# IMX8_PWR.net
KiCad netlist of a schematic drawn in Altium Designer
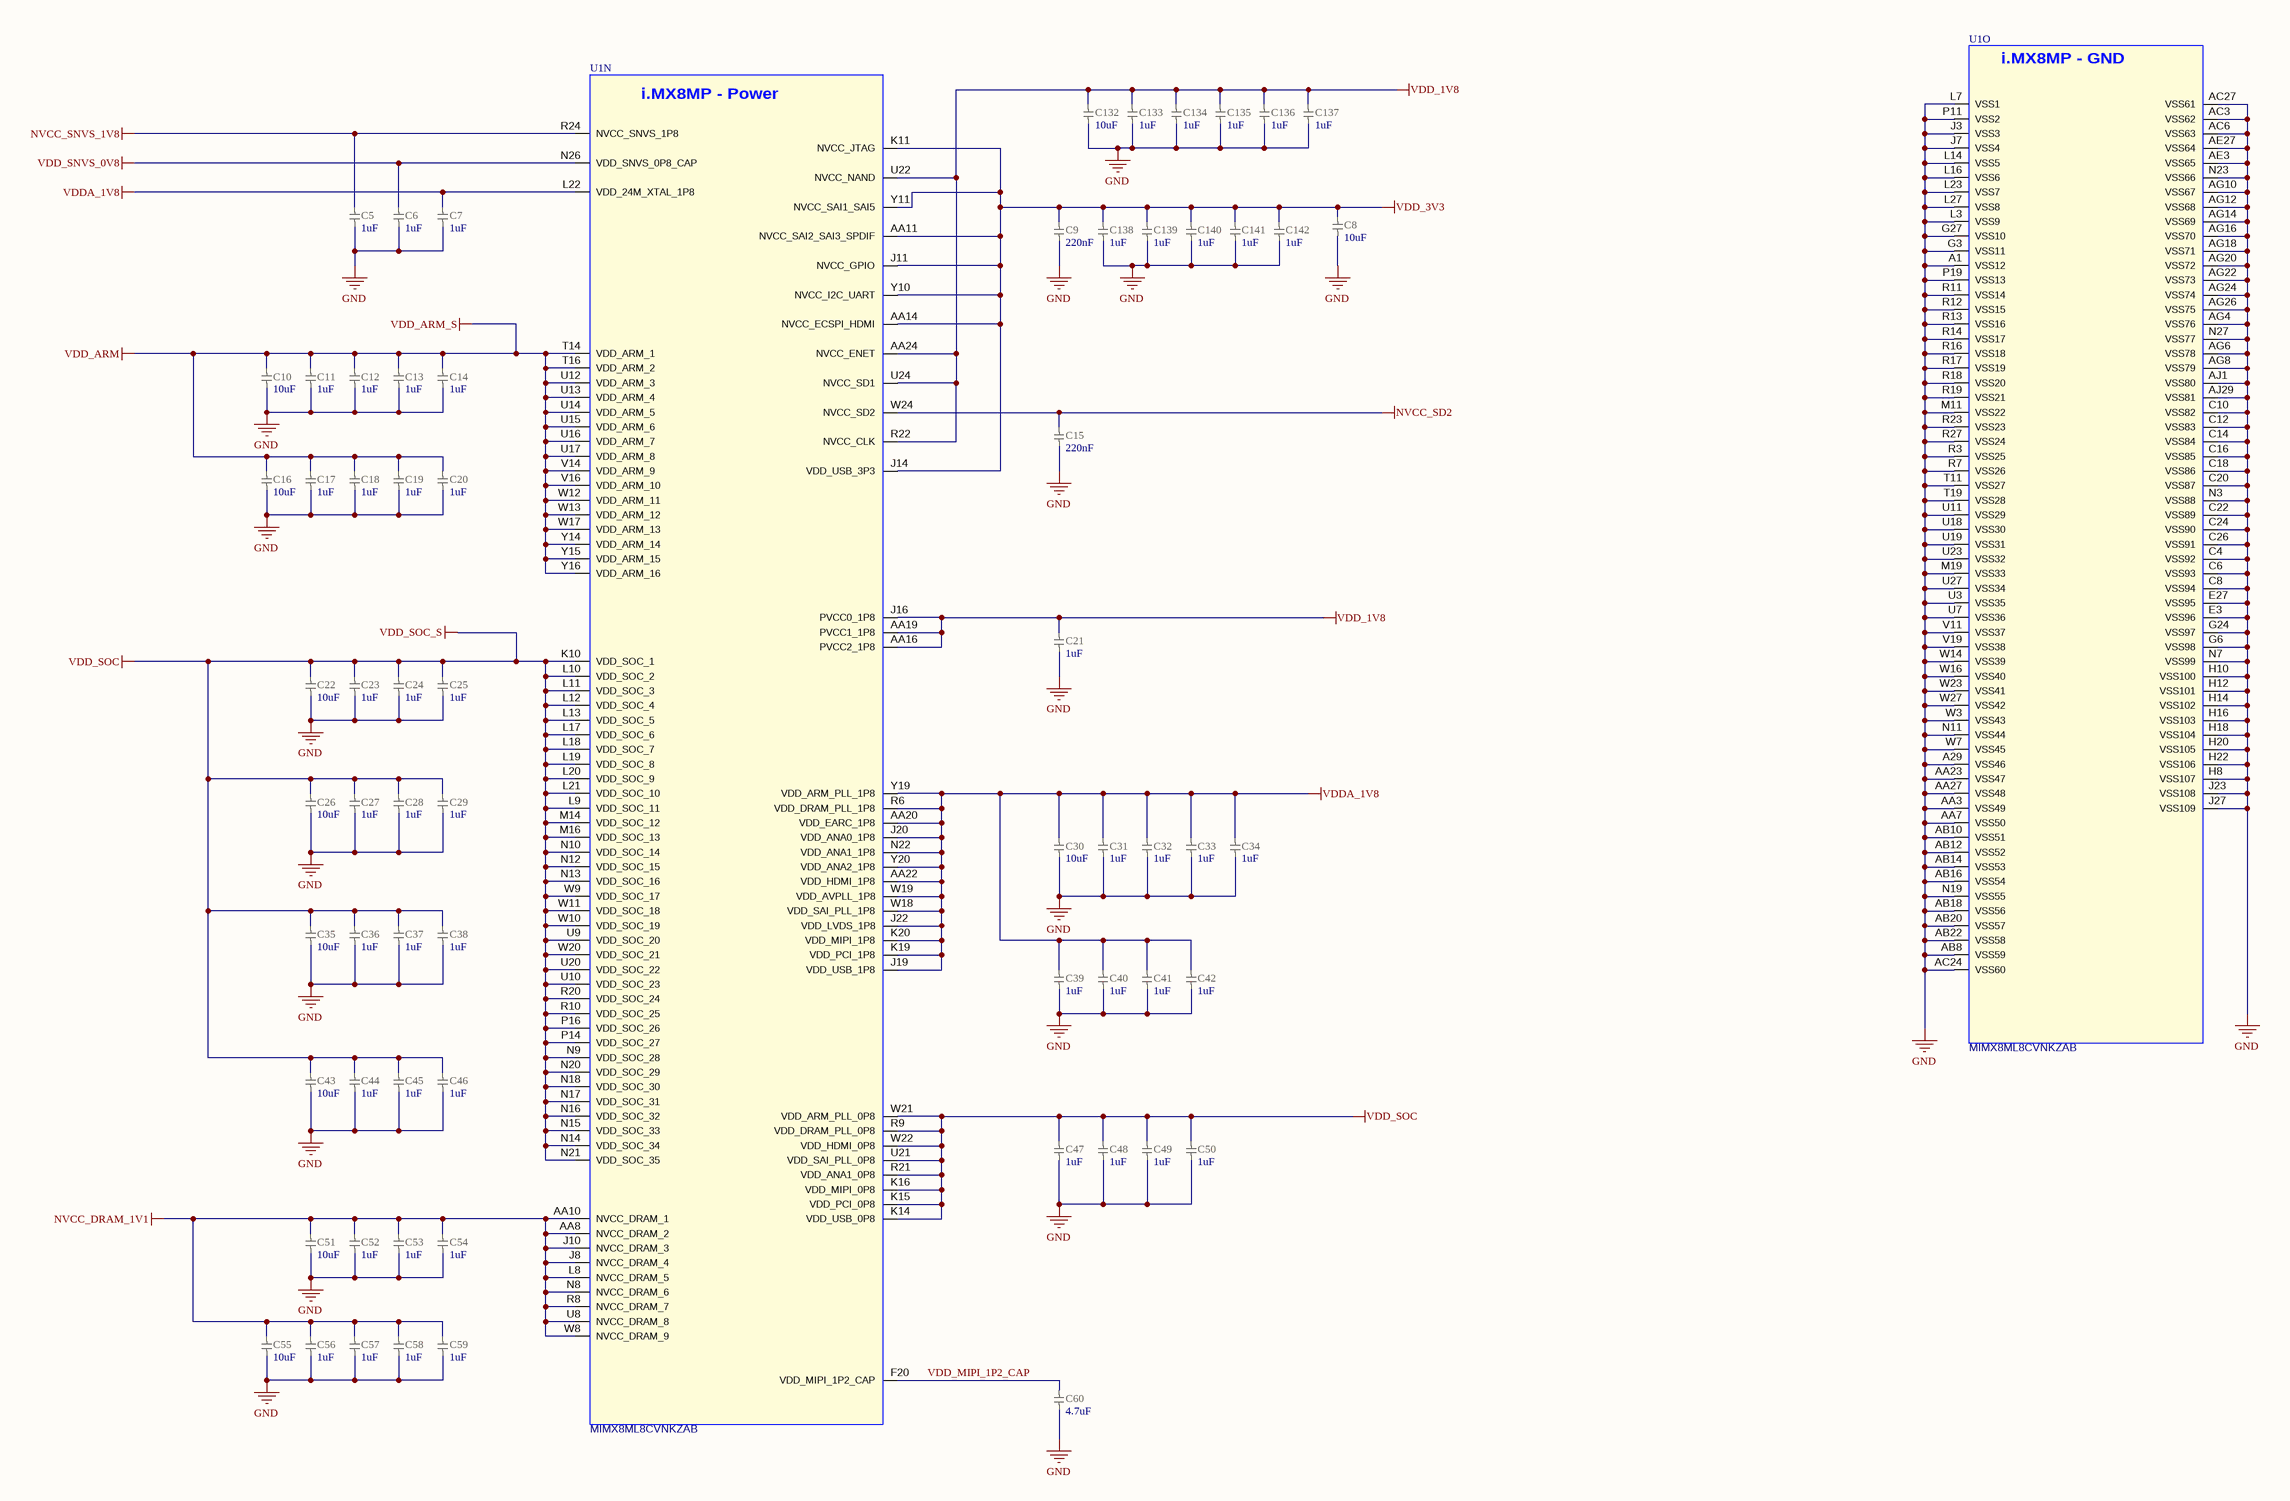
[diagram p0: IMX8_PWR.SchDoc]

(export (version "E")
  (design (tool "Eeschema 10.0.6"))
  (components
    (comp (ref "C5")
      (value "1uF")
      (footprint "CAP_0201_UN1Q")
      (description "CAP")
      (fields (field (name "PART NUMBER") "KGM03CS61A105MH") (field (name "MANUFACTURER") "KYOCERA AVX"))
      (libsource (lib "robo_cam") (part "CMP-001-000336-15"))
    )
    (comp (ref "C6")
      (value "1uF")
      (footprint "CAP_0201_UN1Q")
      (description "CAP")
      (fields (field (name "PART NUMBER") "KGM03CS61A105MH") (field (name "MANUFACTURER") "KYOCERA AVX"))
      (libsource (lib "robo_cam") (part "CMP-001-000336-15"))
    )
    (comp (ref "C7")
      (value "1uF")
      (footprint "CAP_0201_UN1Q")
      (description "CAP")
      (fields (field (name "PART NUMBER") "KGM03CS61A105MH") (field (name "MANUFACTURER") "KYOCERA AVX"))
      (libsource (lib "robo_cam") (part "CMP-001-000336-15"))
    )
    (comp (ref "C8")
      (value "10uF")
      (footprint "CAP_0402_H09W07_UN1Q")
      (description "CAP")
      (fields (field (name "VOLTAGE") "6.3V") (field (name "TOLERANCE") "+/-20%"))
      (libsource (lib "robo_cam") (part "CMP-001-000883-14"))
    )
    (comp (ref "C9")
      (value "220nF")
      (footprint "CAP_0201_UN1Q")
      (description "CAP")
      (fields (field (name "PART NUMBER") "GRM033C81A224KE01D") (field (name "MANUFACTURER") "Murata"))
      (libsource (lib "robo_cam") (part "CMP-001-000889-11"))
    )
    (comp (ref "C10")
      (value "10uF")
      (footprint "CAP_0402_H09W07_UN1Q")
      (description "CAP")
      (fields (field (name "VOLTAGE") "6.3V") (field (name "TOLERANCE") "+/-20%"))
      (libsource (lib "robo_cam") (part "CMP-001-000883-14"))
    )
    (comp (ref "C11")
      (value "1uF")
      (footprint "CAP_0201_UN1Q")
      (description "CAP")
      (fields (field (name "PART NUMBER") "KGM03CS61A105MH") (field (name "MANUFACTURER") "KYOCERA AVX"))
      (libsource (lib "robo_cam") (part "CMP-001-000336-15"))
    )
    (comp (ref "C12")
      (value "1uF")
      (footprint "CAP_0201_UN1Q")
      (description "CAP")
      (fields (field (name "PART NUMBER") "KGM03CS61A105MH") (field (name "MANUFACTURER") "KYOCERA AVX"))
      (libsource (lib "robo_cam") (part "CMP-001-000336-15"))
    )
    (comp (ref "C13")
      (value "1uF")
      (footprint "CAP_0201_UN1Q")
      (description "CAP")
      (fields (field (name "PART NUMBER") "KGM03CS61A105MH") (field (name "MANUFACTURER") "KYOCERA AVX"))
      (libsource (lib "robo_cam") (part "CMP-001-000336-15"))
    )
    (comp (ref "C14")
      (value "1uF")
      (footprint "CAP_0201_UN1Q")
      (description "CAP")
      (fields (field (name "PART NUMBER") "KGM03CS61A105MH") (field (name "MANUFACTURER") "KYOCERA AVX"))
      (libsource (lib "robo_cam") (part "CMP-001-000336-15"))
    )
    (comp (ref "C15")
      (value "220nF")
      (footprint "CAP_0201_UN1Q")
      (description "CAP")
      (fields (field (name "PART NUMBER") "GRM033C81A224KE01D") (field (name "MANUFACTURER") "Murata"))
      (libsource (lib "robo_cam") (part "CMP-001-000889-11"))
    )
    (comp (ref "C16")
      (value "10uF")
      (footprint "CAP_0402_H09W07_UN1Q")
      (description "CAP")
      (fields (field (name "VOLTAGE") "6.3V") (field (name "TOLERANCE") "+/-20%"))
      (libsource (lib "robo_cam") (part "CMP-001-000883-14"))
    )
    (comp (ref "C17")
      (value "1uF")
      (footprint "CAP_0201_UN1Q")
      (description "CAP")
      (fields (field (name "PART NUMBER") "KGM03CS61A105MH") (field (name "MANUFACTURER") "KYOCERA AVX"))
      (libsource (lib "robo_cam") (part "CMP-001-000336-15"))
    )
    (comp (ref "C18")
      (value "1uF")
      (footprint "CAP_0201_UN1Q")
      (description "CAP")
      (fields (field (name "PART NUMBER") "KGM03CS61A105MH") (field (name "MANUFACTURER") "KYOCERA AVX"))
      (libsource (lib "robo_cam") (part "CMP-001-000336-15"))
    )
    (comp (ref "C19")
      (value "1uF")
      (footprint "CAP_0201_UN1Q")
      (description "CAP")
      (fields (field (name "PART NUMBER") "KGM03CS61A105MH") (field (name "MANUFACTURER") "KYOCERA AVX"))
      (libsource (lib "robo_cam") (part "CMP-001-000336-15"))
    )
    (comp (ref "C20")
      (value "1uF")
      (footprint "CAP_0201_UN1Q")
      (description "CAP")
      (fields (field (name "PART NUMBER") "KGM03CS61A105MH") (field (name "MANUFACTURER") "KYOCERA AVX"))
      (libsource (lib "robo_cam") (part "CMP-001-000336-15"))
    )
    (comp (ref "C21")
      (value "1uF")
      (footprint "CAP_0201_UN1Q")
      (description "CAP")
      (fields (field (name "PART NUMBER") "KGM03CS61A105MH") (field (name "MANUFACTURER") "KYOCERA AVX"))
      (libsource (lib "robo_cam") (part "CMP-001-000336-15"))
    )
    (comp (ref "C22")
      (value "10uF")
      (footprint "CAP_0402_H09W07_UN1Q")
      (description "CAP")
      (fields (field (name "VOLTAGE") "6.3V") (field (name "TOLERANCE") "+/-20%"))
      (libsource (lib "robo_cam") (part "CMP-001-000883-14"))
    )
    (comp (ref "C23")
      (value "1uF")
      (footprint "CAP_0201_UN1Q")
      (description "CAP")
      (fields (field (name "PART NUMBER") "KGM03CS61A105MH") (field (name "MANUFACTURER") "KYOCERA AVX"))
      (libsource (lib "robo_cam") (part "CMP-001-000336-15"))
    )
    (comp (ref "C24")
      (value "1uF")
      (footprint "CAP_0201_UN1Q")
      (description "CAP")
      (fields (field (name "PART NUMBER") "KGM03CS61A105MH") (field (name "MANUFACTURER") "KYOCERA AVX"))
      (libsource (lib "robo_cam") (part "CMP-001-000336-15"))
    )
    (comp (ref "C25")
      (value "1uF")
      (footprint "CAP_0201_UN1Q")
      (description "CAP")
      (fields (field (name "PART NUMBER") "KGM03CS61A105MH") (field (name "MANUFACTURER") "KYOCERA AVX"))
      (libsource (lib "robo_cam") (part "CMP-001-000336-15"))
    )
    (comp (ref "C26")
      (value "10uF")
      (footprint "CAP_0402_H09W07_UN1Q")
      (description "CAP")
      (fields (field (name "VOLTAGE") "6.3V") (field (name "TOLERANCE") "+/-20%"))
      (libsource (lib "robo_cam") (part "CMP-001-000883-14"))
    )
    (comp (ref "C27")
      (value "1uF")
      (footprint "CAP_0201_UN1Q")
      (description "CAP")
      (fields (field (name "PART NUMBER") "KGM03CS61A105MH") (field (name "MANUFACTURER") "KYOCERA AVX"))
      (libsource (lib "robo_cam") (part "CMP-001-000336-15"))
    )
    (comp (ref "C28")
      (value "1uF")
      (footprint "CAP_0201_UN1Q")
      (description "CAP")
      (fields (field (name "PART NUMBER") "KGM03CS61A105MH") (field (name "MANUFACTURER") "KYOCERA AVX"))
      (libsource (lib "robo_cam") (part "CMP-001-000336-15"))
    )
    (comp (ref "C29")
      (value "1uF")
      (footprint "CAP_0201_UN1Q")
      (description "CAP")
      (fields (field (name "PART NUMBER") "KGM03CS61A105MH") (field (name "MANUFACTURER") "KYOCERA AVX"))
      (libsource (lib "robo_cam") (part "CMP-001-000336-15"))
    )
    (comp (ref "C30")
      (value "10uF")
      (footprint "CAP_0402_H09W07_UN1Q")
      (description "CAP")
      (fields (field (name "VOLTAGE") "6.3V") (field (name "TOLERANCE") "+/-20%"))
      (libsource (lib "robo_cam") (part "CMP-001-000883-14"))
    )
    (comp (ref "C31")
      (value "1uF")
      (footprint "CAP_0201_UN1Q")
      (description "CAP")
      (fields (field (name "PART NUMBER") "KGM03CS61A105MH") (field (name "MANUFACTURER") "KYOCERA AVX"))
      (libsource (lib "robo_cam") (part "CMP-001-000336-15"))
    )
    (comp (ref "C32")
      (value "1uF")
      (footprint "CAP_0201_UN1Q")
      (description "CAP")
      (fields (field (name "PART NUMBER") "KGM03CS61A105MH") (field (name "MANUFACTURER") "KYOCERA AVX"))
      (libsource (lib "robo_cam") (part "CMP-001-000336-15"))
    )
    (comp (ref "C33")
      (value "1uF")
      (footprint "CAP_0201_UN1Q")
      (description "CAP")
      (fields (field (name "PART NUMBER") "KGM03CS61A105MH") (field (name "MANUFACTURER") "KYOCERA AVX"))
      (libsource (lib "robo_cam") (part "CMP-001-000336-15"))
    )
    (comp (ref "C34")
      (value "1uF")
      (footprint "CAP_0201_UN1Q")
      (description "CAP")
      (fields (field (name "PART NUMBER") "KGM03CS61A105MH") (field (name "MANUFACTURER") "KYOCERA AVX"))
      (libsource (lib "robo_cam") (part "CMP-001-000336-15"))
    )
    (comp (ref "C35")
      (value "10uF")
      (footprint "CAP_0402_H09W07_UN1Q")
      (description "CAP")
      (fields (field (name "VOLTAGE") "6.3V") (field (name "TOLERANCE") "+/-20%"))
      (libsource (lib "robo_cam") (part "CMP-001-000883-14"))
    )
    (comp (ref "C36")
      (value "1uF")
      (footprint "CAP_0201_UN1Q")
      (description "CAP")
      (fields (field (name "PART NUMBER") "KGM03CS61A105MH") (field (name "MANUFACTURER") "KYOCERA AVX"))
      (libsource (lib "robo_cam") (part "CMP-001-000336-15"))
    )
    (comp (ref "C37")
      (value "1uF")
      (footprint "CAP_0201_UN1Q")
      (description "CAP")
      (fields (field (name "PART NUMBER") "KGM03CS61A105MH") (field (name "MANUFACTURER") "KYOCERA AVX"))
      (libsource (lib "robo_cam") (part "CMP-001-000336-15"))
    )
    (comp (ref "C38")
      (value "1uF")
      (footprint "CAP_0201_UN1Q")
      (description "CAP")
      (fields (field (name "PART NUMBER") "KGM03CS61A105MH") (field (name "MANUFACTURER") "KYOCERA AVX"))
      (libsource (lib "robo_cam") (part "CMP-001-000336-15"))
    )
    (comp (ref "C39")
      (value "1uF")
      (footprint "CAP_0201_UN1Q")
      (description "CAP")
      (fields (field (name "PART NUMBER") "KGM03CS61A105MH") (field (name "MANUFACTURER") "KYOCERA AVX"))
      (libsource (lib "robo_cam") (part "CMP-001-000336-15"))
    )
    (comp (ref "C40")
      (value "1uF")
      (footprint "CAP_0201_UN1Q")
      (description "CAP")
      (fields (field (name "PART NUMBER") "KGM03CS61A105MH") (field (name "MANUFACTURER") "KYOCERA AVX"))
      (libsource (lib "robo_cam") (part "CMP-001-000336-15"))
    )
    (comp (ref "C41")
      (value "1uF")
      (footprint "CAP_0201_UN1Q")
      (description "CAP")
      (fields (field (name "PART NUMBER") "KGM03CS61A105MH") (field (name "MANUFACTURER") "KYOCERA AVX"))
      (libsource (lib "robo_cam") (part "CMP-001-000336-15"))
    )
    (comp (ref "C42")
      (value "1uF")
      (footprint "CAP_0201_UN1Q")
      (description "CAP")
      (fields (field (name "PART NUMBER") "KGM03CS61A105MH") (field (name "MANUFACTURER") "KYOCERA AVX"))
      (libsource (lib "robo_cam") (part "CMP-001-000336-15"))
    )
    (comp (ref "C43")
      (value "10uF")
      (footprint "CAP_0402_H09W07_UN1Q")
      (description "CAP")
      (fields (field (name "VOLTAGE") "6.3V") (field (name "TOLERANCE") "+/-20%"))
      (libsource (lib "robo_cam") (part "CMP-001-000883-14"))
    )
    (comp (ref "C44")
      (value "1uF")
      (footprint "CAP_0201_UN1Q")
      (description "CAP")
      (fields (field (name "PART NUMBER") "KGM03CS61A105MH") (field (name "MANUFACTURER") "KYOCERA AVX"))
      (libsource (lib "robo_cam") (part "CMP-001-000336-15"))
    )
    (comp (ref "C45")
      (value "1uF")
      (footprint "CAP_0201_UN1Q")
      (description "CAP")
      (fields (field (name "PART NUMBER") "KGM03CS61A105MH") (field (name "MANUFACTURER") "KYOCERA AVX"))
      (libsource (lib "robo_cam") (part "CMP-001-000336-15"))
    )
    (comp (ref "C46")
      (value "1uF")
      (footprint "CAP_0201_UN1Q")
      (description "CAP")
      (fields (field (name "PART NUMBER") "KGM03CS61A105MH") (field (name "MANUFACTURER") "KYOCERA AVX"))
      (libsource (lib "robo_cam") (part "CMP-001-000336-15"))
    )
    (comp (ref "C47")
      (value "1uF")
      (footprint "CAP_0201_UN1Q")
      (description "CAP")
      (fields (field (name "PART NUMBER") "KGM03CS61A105MH") (field (name "MANUFACTURER") "KYOCERA AVX"))
      (libsource (lib "robo_cam") (part "CMP-001-000336-15"))
    )
    (comp (ref "C48")
      (value "1uF")
      (footprint "CAP_0201_UN1Q")
      (description "CAP")
      (fields (field (name "PART NUMBER") "KGM03CS61A105MH") (field (name "MANUFACTURER") "KYOCERA AVX"))
      (libsource (lib "robo_cam") (part "CMP-001-000336-15"))
    )
    (comp (ref "C49")
      (value "1uF")
      (footprint "CAP_0201_UN1Q")
      (description "CAP")
      (fields (field (name "PART NUMBER") "KGM03CS61A105MH") (field (name "MANUFACTURER") "KYOCERA AVX"))
      (libsource (lib "robo_cam") (part "CMP-001-000336-15"))
    )
    (comp (ref "C50")
      (value "1uF")
      (footprint "CAP_0201_UN1Q")
      (description "CAP")
      (fields (field (name "PART NUMBER") "KGM03CS61A105MH") (field (name "MANUFACTURER") "KYOCERA AVX"))
      (libsource (lib "robo_cam") (part "CMP-001-000336-15"))
    )
    (comp (ref "C51")
      (value "10uF")
      (footprint "CAP_0402_H09W07_UN1Q")
      (description "CAP")
      (fields (field (name "VOLTAGE") "6.3V") (field (name "TOLERANCE") "+/-20%"))
      (libsource (lib "robo_cam") (part "CMP-001-000883-14"))
    )
    (comp (ref "C52")
      (value "1uF")
      (footprint "CAP_0201_UN1Q")
      (description "CAP")
      (fields (field (name "PART NUMBER") "KGM03CS61A105MH") (field (name "MANUFACTURER") "KYOCERA AVX"))
      (libsource (lib "robo_cam") (part "CMP-001-000336-15"))
    )
    (comp (ref "C53")
      (value "1uF")
      (footprint "CAP_0201_UN1Q")
      (description "CAP")
      (fields (field (name "PART NUMBER") "KGM03CS61A105MH") (field (name "MANUFACTURER") "KYOCERA AVX"))
      (libsource (lib "robo_cam") (part "CMP-001-000336-15"))
    )
    (comp (ref "C54")
      (value "1uF")
      (footprint "CAP_0201_UN1Q")
      (description "CAP")
      (fields (field (name "PART NUMBER") "KGM03CS61A105MH") (field (name "MANUFACTURER") "KYOCERA AVX"))
      (libsource (lib "robo_cam") (part "CMP-001-000336-15"))
    )
    (comp (ref "C55")
      (value "10uF")
      (footprint "CAP_0402_H09W07_UN1Q")
      (description "CAP")
      (fields (field (name "VOLTAGE") "6.3V") (field (name "TOLERANCE") "+/-20%"))
      (libsource (lib "robo_cam") (part "CMP-001-000883-14"))
    )
    (comp (ref "C56")
      (value "1uF")
      (footprint "CAP_0201_UN1Q")
      (description "CAP")
      (fields (field (name "PART NUMBER") "KGM03CS61A105MH") (field (name "MANUFACTURER") "KYOCERA AVX"))
      (libsource (lib "robo_cam") (part "CMP-001-000336-15"))
    )
    (comp (ref "C57")
      (value "1uF")
      (footprint "CAP_0201_UN1Q")
      (description "CAP")
      (fields (field (name "PART NUMBER") "KGM03CS61A105MH") (field (name "MANUFACTURER") "KYOCERA AVX"))
      (libsource (lib "robo_cam") (part "CMP-001-000336-15"))
    )
    (comp (ref "C58")
      (value "1uF")
      (footprint "CAP_0201_UN1Q")
      (description "CAP")
      (fields (field (name "PART NUMBER") "KGM03CS61A105MH") (field (name "MANUFACTURER") "KYOCERA AVX"))
      (libsource (lib "robo_cam") (part "CMP-001-000336-15"))
    )
    (comp (ref "C59")
      (value "1uF")
      (footprint "CAP_0201_UN1Q")
      (description "CAP")
      (fields (field (name "PART NUMBER") "KGM03CS61A105MH") (field (name "MANUFACTURER") "KYOCERA AVX"))
      (libsource (lib "robo_cam") (part "CMP-001-000336-15"))
    )
    (comp (ref "C60")
      (value "4.7uF")
      (footprint "CAP_0402_H09W07_UN1Q")
      (description "CAP")
      (fields (field (name "PART NUMBER") "GRT155C81A475ME13J") (field (name "MANUFACTURER") "Murata"))
      (libsource (lib "robo_cam") (part "CMP-001-000888-12"))
    )
    (comp (ref "C132")
      (value "10uF")
      (footprint "CAP_0402_H09W07_UN1Q")
      (description "CAP")
      (fields (field (name "VOLTAGE") "6.3V") (field (name "TOLERANCE") "+/-20%"))
      (libsource (lib "robo_cam") (part "CMP-001-000883-14"))
    )
    (comp (ref "C133")
      (value "1uF")
      (footprint "CAP_0201_UN1Q")
      (description "CAP")
      (fields (field (name "PART NUMBER") "KGM03CS61A105MH") (field (name "MANUFACTURER") "KYOCERA AVX"))
      (libsource (lib "robo_cam") (part "CMP-001-000336-15"))
    )
    (comp (ref "C134")
      (value "1uF")
      (footprint "CAP_0201_UN1Q")
      (description "CAP")
      (fields (field (name "PART NUMBER") "KGM03CS61A105MH") (field (name "MANUFACTURER") "KYOCERA AVX"))
      (libsource (lib "robo_cam") (part "CMP-001-000336-15"))
    )
    (comp (ref "C135")
      (value "1uF")
      (footprint "CAP_0201_UN1Q")
      (description "CAP")
      (fields (field (name "PART NUMBER") "KGM03CS61A105MH") (field (name "MANUFACTURER") "KYOCERA AVX"))
      (libsource (lib "robo_cam") (part "CMP-001-000336-15"))
    )
    (comp (ref "C136")
      (value "1uF")
      (footprint "CAP_0201_UN1Q")
      (description "CAP")
      (fields (field (name "PART NUMBER") "KGM03CS61A105MH") (field (name "MANUFACTURER") "KYOCERA AVX"))
      (libsource (lib "robo_cam") (part "CMP-001-000336-15"))
    )
    (comp (ref "C137")
      (value "1uF")
      (footprint "CAP_0201_UN1Q")
      (description "CAP")
      (fields (field (name "PART NUMBER") "KGM03CS61A105MH") (field (name "MANUFACTURER") "KYOCERA AVX"))
      (libsource (lib "robo_cam") (part "CMP-001-000336-15"))
    )
    (comp (ref "C138")
      (value "1uF")
      (footprint "CAP_0201_UN1Q")
      (description "CAP")
      (fields (field (name "PART NUMBER") "KGM03CS61A105MH") (field (name "MANUFACTURER") "KYOCERA AVX"))
      (libsource (lib "robo_cam") (part "CMP-001-000336-15"))
    )
    (comp (ref "C139")
      (value "1uF")
      (footprint "CAP_0201_UN1Q")
      (description "CAP")
      (fields (field (name "PART NUMBER") "KGM03CS61A105MH") (field (name "MANUFACTURER") "KYOCERA AVX"))
      (libsource (lib "robo_cam") (part "CMP-001-000336-15"))
    )
    (comp (ref "C140")
      (value "1uF")
      (footprint "CAP_0201_UN1Q")
      (description "CAP")
      (fields (field (name "PART NUMBER") "KGM03CS61A105MH") (field (name "MANUFACTURER") "KYOCERA AVX"))
      (libsource (lib "robo_cam") (part "CMP-001-000336-15"))
    )
    (comp (ref "C141")
      (value "1uF")
      (footprint "CAP_0201_UN1Q")
      (description "CAP")
      (fields (field (name "PART NUMBER") "KGM03CS61A105MH") (field (name "MANUFACTURER") "KYOCERA AVX"))
      (libsource (lib "robo_cam") (part "CMP-001-000336-15"))
    )
    (comp (ref "C142")
      (value "1uF")
      (footprint "CAP_0201_UN1Q")
      (description "CAP")
      (fields (field (name "PART NUMBER") "KGM03CS61A105MH") (field (name "MANUFACTURER") "KYOCERA AVX"))
      (libsource (lib "robo_cam") (part "CMP-001-000336-15"))
    )
    (comp (ref "U1")
      (value "MIMX8ML8CVNKZAB")
      (footprint "BGA548C50P29X29_1500X1500X148")
      (description "CPU QUAD CORTEX A53+M4 1.6GHZ BGA548 Industrial")
      (fields
        (field (name "MANUFACTURER") "NXP Semiconductors")
        (field (name "PART NUMBER") "MIMX8ML8CVNKZAB")
        (field (name "SOURCE") "UUDET_KOMPONENTIT.SchLib")
      )
      (libsource (lib "robo_cam") (part "CMP-001-000983-8"))
    )
  )
  (nets
    (net (code "1") (name "/VDD_MIPI_1P2_CAP") (class "Default")
      (node (ref "C60") (pin "2") (pinfunction "2_2") (pintype "passive"))
      (node (ref "U1") (pin "F20") (pinfunction "VDD_MIPI_1P2_CAP_F20") (pintype "power_in"))
    )
    (net (code "2") (name "GND") (class "Default")
      (node (ref "C10") (pin "1") (pinfunction "1_1") (pintype "passive"))
      (node (ref "C11") (pin "1") (pinfunction "1_1") (pintype "passive"))
      (node (ref "C12") (pin "1") (pinfunction "1_1") (pintype "passive"))
      (node (ref "C13") (pin "1") (pinfunction "1_1") (pintype "passive"))
      (node (ref "C132") (pin "1") (pinfunction "1_1") (pintype "passive"))
      (node (ref "C133") (pin "1") (pinfunction "1_1") (pintype "passive"))
      (node (ref "C134") (pin "1") (pinfunction "1_1") (pintype "passive"))
      (node (ref "C135") (pin "1") (pinfunction "1_1") (pintype "passive"))
      (node (ref "C136") (pin "1") (pinfunction "1_1") (pintype "passive"))
      (node (ref "C137") (pin "1") (pinfunction "1_1") (pintype "passive"))
      (node (ref "C138") (pin "1") (pinfunction "1_1") (pintype "passive"))
      (node (ref "C139") (pin "1") (pinfunction "1_1") (pintype "passive"))
      (node (ref "C14") (pin "1") (pinfunction "1_1") (pintype "passive"))
      (node (ref "C140") (pin "1") (pinfunction "1_1") (pintype "passive"))
      (node (ref "C141") (pin "1") (pinfunction "1_1") (pintype "passive"))
      (node (ref "C142") (pin "1") (pinfunction "1_1") (pintype "passive"))
      (node (ref "C15") (pin "1") (pinfunction "1_1") (pintype "passive"))
      (node (ref "C16") (pin "1") (pinfunction "1_1") (pintype "passive"))
      (node (ref "C17") (pin "1") (pinfunction "1_1") (pintype "passive"))
      (node (ref "C18") (pin "1") (pinfunction "1_1") (pintype "passive"))
      (node (ref "C19") (pin "1") (pinfunction "1_1") (pintype "passive"))
      (node (ref "C20") (pin "1") (pinfunction "1_1") (pintype "passive"))
      (node (ref "C21") (pin "1") (pinfunction "1_1") (pintype "passive"))
      (node (ref "C22") (pin "1") (pinfunction "1_1") (pintype "passive"))
      (node (ref "C23") (pin "1") (pinfunction "1_1") (pintype "passive"))
      (node (ref "C24") (pin "1") (pinfunction "1_1") (pintype "passive"))
      (node (ref "C25") (pin "1") (pinfunction "1_1") (pintype "passive"))
      (node (ref "C26") (pin "1") (pinfunction "1_1") (pintype "passive"))
      (node (ref "C27") (pin "1") (pinfunction "1_1") (pintype "passive"))
      (node (ref "C28") (pin "1") (pinfunction "1_1") (pintype "passive"))
      (node (ref "C29") (pin "1") (pinfunction "1_1") (pintype "passive"))
      (node (ref "C30") (pin "1") (pinfunction "1_1") (pintype "passive"))
      (node (ref "C31") (pin "1") (pinfunction "1_1") (pintype "passive"))
      (node (ref "C32") (pin "1") (pinfunction "1_1") (pintype "passive"))
      (node (ref "C33") (pin "1") (pinfunction "1_1") (pintype "passive"))
      (node (ref "C34") (pin "1") (pinfunction "1_1") (pintype "passive"))
      (node (ref "C35") (pin "1") (pinfunction "1_1") (pintype "passive"))
      (node (ref "C36") (pin "1") (pinfunction "1_1") (pintype "passive"))
      (node (ref "C37") (pin "1") (pinfunction "1_1") (pintype "passive"))
      (node (ref "C38") (pin "1") (pinfunction "1_1") (pintype "passive"))
      (node (ref "C39") (pin "1") (pinfunction "1_1") (pintype "passive"))
      (node (ref "C40") (pin "1") (pinfunction "1_1") (pintype "passive"))
      (node (ref "C41") (pin "1") (pinfunction "1_1") (pintype "passive"))
      (node (ref "C42") (pin "1") (pinfunction "1_1") (pintype "passive"))
      (node (ref "C43") (pin "1") (pinfunction "1_1") (pintype "passive"))
      (node (ref "C44") (pin "1") (pinfunction "1_1") (pintype "passive"))
      (node (ref "C45") (pin "1") (pinfunction "1_1") (pintype "passive"))
      (node (ref "C46") (pin "1") (pinfunction "1_1") (pintype "passive"))
      (node (ref "C47") (pin "1") (pinfunction "1_1") (pintype "passive"))
      (node (ref "C48") (pin "1") (pinfunction "1_1") (pintype "passive"))
      (node (ref "C49") (pin "1") (pinfunction "1_1") (pintype "passive"))
      (node (ref "C5") (pin "1") (pinfunction "1_1") (pintype "passive"))
      (node (ref "C50") (pin "1") (pinfunction "1_1") (pintype "passive"))
      (node (ref "C51") (pin "1") (pinfunction "1_1") (pintype "passive"))
      (node (ref "C52") (pin "1") (pinfunction "1_1") (pintype "passive"))
      (node (ref "C53") (pin "1") (pinfunction "1_1") (pintype "passive"))
      (node (ref "C54") (pin "1") (pinfunction "1_1") (pintype "passive"))
      (node (ref "C55") (pin "1") (pinfunction "1_1") (pintype "passive"))
      (node (ref "C56") (pin "1") (pinfunction "1_1") (pintype "passive"))
      (node (ref "C57") (pin "1") (pinfunction "1_1") (pintype "passive"))
      (node (ref "C58") (pin "1") (pinfunction "1_1") (pintype "passive"))
      (node (ref "C59") (pin "1") (pinfunction "1_1") (pintype "passive"))
      (node (ref "C6") (pin "1") (pinfunction "1_1") (pintype "passive"))
      (node (ref "C60") (pin "1") (pinfunction "1_1") (pintype "passive"))
      (node (ref "C7") (pin "1") (pinfunction "1_1") (pintype "passive"))
      (node (ref "C8") (pin "1") (pinfunction "1_1") (pintype "passive"))
      (node (ref "C9") (pin "1") (pinfunction "1_1") (pintype "passive"))
      (node (ref "U1") (pin "A1") (pinfunction "VSS12_A1") (pintype "power_in"))
      (node (ref "U1") (pin "A29") (pinfunction "VSS46_A29") (pintype "power_in"))
      (node (ref "U1") (pin "AA23") (pinfunction "VSS47_AA23") (pintype "power_in"))
      (node (ref "U1") (pin "AA27") (pinfunction "VSS48_AA27") (pintype "power_in"))
      (node (ref "U1") (pin "AA3") (pinfunction "VSS49_AA3") (pintype "power_in"))
      (node (ref "U1") (pin "AA7") (pinfunction "VSS50_AA7") (pintype "power_in"))
      (node (ref "U1") (pin "AB10") (pinfunction "VSS51_AB10") (pintype "power_in"))
      (node (ref "U1") (pin "AB12") (pinfunction "VSS52_AB12") (pintype "power_in"))
      (node (ref "U1") (pin "AB14") (pinfunction "VSS53_AB14") (pintype "power_in"))
      (node (ref "U1") (pin "AB16") (pinfunction "VSS54_AB16") (pintype "power_in"))
      (node (ref "U1") (pin "AB18") (pinfunction "VSS56_AB18") (pintype "power_in"))
      (node (ref "U1") (pin "AB20") (pinfunction "VSS57_AB20") (pintype "power_in"))
      (node (ref "U1") (pin "AB22") (pinfunction "VSS58_AB22") (pintype "power_in"))
      (node (ref "U1") (pin "AB8") (pinfunction "VSS59_AB8") (pintype "power_in"))
      (node (ref "U1") (pin "AC24") (pinfunction "VSS60_AC24") (pintype "power_in"))
      (node (ref "U1") (pin "AC27") (pinfunction "VSS61_AC27") (pintype "power_in"))
      (node (ref "U1") (pin "AC3") (pinfunction "VSS62_AC3") (pintype "power_in"))
      (node (ref "U1") (pin "AC6") (pinfunction "VSS63_AC6") (pintype "power_in"))
      (node (ref "U1") (pin "AE27") (pinfunction "VSS64_AE27") (pintype "power_in"))
      (node (ref "U1") (pin "AE3") (pinfunction "VSS65_AE3") (pintype "power_in"))
      (node (ref "U1") (pin "AG10") (pinfunction "VSS67_AG10") (pintype "power_in"))
      (node (ref "U1") (pin "AG12") (pinfunction "VSS68_AG12") (pintype "power_in"))
      (node (ref "U1") (pin "AG14") (pinfunction "VSS69_AG14") (pintype "power_in"))
      (node (ref "U1") (pin "AG16") (pinfunction "VSS70_AG16") (pintype "power_in"))
      (node (ref "U1") (pin "AG18") (pinfunction "VSS71_AG18") (pintype "power_in"))
      (node (ref "U1") (pin "AG20") (pinfunction "VSS72_AG20") (pintype "power_in"))
      (node (ref "U1") (pin "AG22") (pinfunction "VSS73_AG22") (pintype "power_in"))
      (node (ref "U1") (pin "AG24") (pinfunction "VSS74_AG24") (pintype "power_in"))
      (node (ref "U1") (pin "AG26") (pinfunction "VSS75_AG26") (pintype "power_in"))
      (node (ref "U1") (pin "AG4") (pinfunction "VSS76_AG4") (pintype "power_in"))
      (node (ref "U1") (pin "AG6") (pinfunction "VSS78_AG6") (pintype "power_in"))
      (node (ref "U1") (pin "AG8") (pinfunction "VSS79_AG8") (pintype "power_in"))
      (node (ref "U1") (pin "AJ1") (pinfunction "VSS80_AJ1") (pintype "power_in"))
      (node (ref "U1") (pin "AJ29") (pinfunction "VSS81_AJ29") (pintype "power_in"))
      (node (ref "U1") (pin "C10") (pinfunction "VSS82_C10") (pintype "power_in"))
      (node (ref "U1") (pin "C12") (pinfunction "VSS83_C12") (pintype "power_in"))
      (node (ref "U1") (pin "C14") (pinfunction "VSS84_C14") (pintype "power_in"))
      (node (ref "U1") (pin "C16") (pinfunction "VSS85_C16") (pintype "power_in"))
      (node (ref "U1") (pin "C18") (pinfunction "VSS86_C18") (pintype "power_in"))
      (node (ref "U1") (pin "C20") (pinfunction "VSS87_C20") (pintype "power_in"))
      (node (ref "U1") (pin "C22") (pinfunction "VSS89_C22") (pintype "power_in"))
      (node (ref "U1") (pin "C24") (pinfunction "VSS90_C24") (pintype "power_in"))
      (node (ref "U1") (pin "C26") (pinfunction "VSS91_C26") (pintype "power_in"))
      (node (ref "U1") (pin "C4") (pinfunction "VSS92_C4") (pintype "power_in"))
      (node (ref "U1") (pin "C6") (pinfunction "VSS93_C6") (pintype "power_in"))
      (node (ref "U1") (pin "C8") (pinfunction "VSS94_C8") (pintype "power_in"))
      (node (ref "U1") (pin "E27") (pinfunction "VSS95_E27") (pintype "power_in"))
      (node (ref "U1") (pin "E3") (pinfunction "VSS96_E3") (pintype "power_in"))
      (node (ref "U1") (pin "G24") (pinfunction "VSS97_G24") (pintype "power_in"))
      (node (ref "U1") (pin "G27") (pinfunction "VSS10_G27") (pintype "power_in"))
      (node (ref "U1") (pin "G3") (pinfunction "VSS11_G3") (pintype "power_in"))
      (node (ref "U1") (pin "G6") (pinfunction "VSS98_G6") (pintype "power_in"))
      (node (ref "U1") (pin "H10") (pinfunction "VSS100_H10") (pintype "power_in"))
      (node (ref "U1") (pin "H12") (pinfunction "VSS101_H12") (pintype "power_in"))
      (node (ref "U1") (pin "H14") (pinfunction "VSS102_H14") (pintype "power_in"))
      (node (ref "U1") (pin "H16") (pinfunction "VSS103_H16") (pintype "power_in"))
      (node (ref "U1") (pin "H18") (pinfunction "VSS104_H18") (pintype "power_in"))
      (node (ref "U1") (pin "H20") (pinfunction "VSS105_H20") (pintype "power_in"))
      (node (ref "U1") (pin "H22") (pinfunction "VSS106_H22") (pintype "power_in"))
      (node (ref "U1") (pin "H8") (pinfunction "VSS107_H8") (pintype "power_in"))
      (node (ref "U1") (pin "J23") (pinfunction "VSS108_J23") (pintype "power_in"))
      (node (ref "U1") (pin "J27") (pinfunction "VSS109_J27") (pintype "power_in"))
      (node (ref "U1") (pin "J3") (pinfunction "VSS3_J3") (pintype "power_in"))
      (node (ref "U1") (pin "J7") (pinfunction "VSS4_J7") (pintype "power_in"))
      (node (ref "U1") (pin "L14") (pinfunction "VSS5_L14") (pintype "power_in"))
      (node (ref "U1") (pin "L16") (pinfunction "VSS6_L16") (pintype "power_in"))
      (node (ref "U1") (pin "L23") (pinfunction "VSS7_L23") (pintype "power_in"))
      (node (ref "U1") (pin "L27") (pinfunction "VSS8_L27") (pintype "power_in"))
      (node (ref "U1") (pin "L3") (pinfunction "VSS9_L3") (pintype "power_in"))
      (node (ref "U1") (pin "L7") (pinfunction "VSS1_L7") (pintype "power_in"))
      (node (ref "U1") (pin "M11") (pinfunction "VSS22_M11") (pintype "power_in"))
      (node (ref "U1") (pin "M19") (pinfunction "VSS33_M19") (pintype "power_in"))
      (node (ref "U1") (pin "N11") (pinfunction "VSS44_N11") (pintype "power_in"))
      (node (ref "U1") (pin "N19") (pinfunction "VSS55_N19") (pintype "power_in"))
      (node (ref "U1") (pin "N23") (pinfunction "VSS66_N23") (pintype "power_in"))
      (node (ref "U1") (pin "N27") (pinfunction "VSS77_N27") (pintype "power_in"))
      (node (ref "U1") (pin "N3") (pinfunction "VSS88_N3") (pintype "power_in"))
      (node (ref "U1") (pin "N7") (pinfunction "VSS99_N7") (pintype "power_in"))
      (node (ref "U1") (pin "P11") (pinfunction "VSS2_P11") (pintype "power_in"))
      (node (ref "U1") (pin "P19") (pinfunction "VSS13_P19") (pintype "power_in"))
      (node (ref "U1") (pin "R11") (pinfunction "VSS14_R11") (pintype "power_in"))
      (node (ref "U1") (pin "R12") (pinfunction "VSS15_R12") (pintype "power_in"))
      (node (ref "U1") (pin "R13") (pinfunction "VSS16_R13") (pintype "power_in"))
      (node (ref "U1") (pin "R14") (pinfunction "VSS17_R14") (pintype "power_in"))
      (node (ref "U1") (pin "R16") (pinfunction "VSS18_R16") (pintype "power_in"))
      (node (ref "U1") (pin "R17") (pinfunction "VSS19_R17") (pintype "power_in"))
      (node (ref "U1") (pin "R18") (pinfunction "VSS20_R18") (pintype "power_in"))
      (node (ref "U1") (pin "R19") (pinfunction "VSS21_R19") (pintype "power_in"))
      (node (ref "U1") (pin "R23") (pinfunction "VSS23_R23") (pintype "power_in"))
      (node (ref "U1") (pin "R27") (pinfunction "VSS24_R27") (pintype "power_in"))
      (node (ref "U1") (pin "R3") (pinfunction "VSS25_R3") (pintype "power_in"))
      (node (ref "U1") (pin "R7") (pinfunction "VSS26_R7") (pintype "power_in"))
      (node (ref "U1") (pin "T11") (pinfunction "VSS27_T11") (pintype "power_in"))
      (node (ref "U1") (pin "T19") (pinfunction "VSS28_T19") (pintype "power_in"))
      (node (ref "U1") (pin "U11") (pinfunction "VSS29_U11") (pintype "power_in"))
      (node (ref "U1") (pin "U18") (pinfunction "VSS30_U18") (pintype "power_in"))
      (node (ref "U1") (pin "U19") (pinfunction "VSS31_U19") (pintype "power_in"))
      (node (ref "U1") (pin "U23") (pinfunction "VSS32_U23") (pintype "power_in"))
      (node (ref "U1") (pin "U27") (pinfunction "VSS34_U27") (pintype "power_in"))
      (node (ref "U1") (pin "U3") (pinfunction "VSS35_U3") (pintype "power_in"))
      (node (ref "U1") (pin "U7") (pinfunction "VSS36_U7") (pintype "power_in"))
      (node (ref "U1") (pin "V11") (pinfunction "VSS37_V11") (pintype "power_in"))
      (node (ref "U1") (pin "V19") (pinfunction "VSS38_V19") (pintype "power_in"))
      (node (ref "U1") (pin "W14") (pinfunction "VSS39_W14") (pintype "power_in"))
      (node (ref "U1") (pin "W16") (pinfunction "VSS40_W16") (pintype "power_in"))
      (node (ref "U1") (pin "W23") (pinfunction "VSS41_W23") (pintype "power_in"))
      (node (ref "U1") (pin "W27") (pinfunction "VSS42_W27") (pintype "power_in"))
      (node (ref "U1") (pin "W3") (pinfunction "VSS43_W3") (pintype "power_in"))
      (node (ref "U1") (pin "W7") (pinfunction "VSS45_W7") (pintype "power_in"))
    )
    (net (code "3") (name "NVCC_DRAM_1V1") (class "Default")
      (node (ref "C51") (pin "2") (pinfunction "2_2") (pintype "passive"))
      (node (ref "C52") (pin "2") (pinfunction "2_2") (pintype "passive"))
      (node (ref "C53") (pin "2") (pinfunction "2_2") (pintype "passive"))
      (node (ref "C54") (pin "2") (pinfunction "2_2") (pintype "passive"))
      (node (ref "C55") (pin "2") (pinfunction "2_2") (pintype "passive"))
      (node (ref "C56") (pin "2") (pinfunction "2_2") (pintype "passive"))
      (node (ref "C57") (pin "2") (pinfunction "2_2") (pintype "passive"))
      (node (ref "C58") (pin "2") (pinfunction "2_2") (pintype "passive"))
      (node (ref "C59") (pin "2") (pinfunction "2_2") (pintype "passive"))
      (node (ref "U1") (pin "AA10") (pinfunction "NVCC_DRAM_1_AA10") (pintype "power_in"))
      (node (ref "U1") (pin "AA8") (pinfunction "NVCC_DRAM_2_AA8") (pintype "power_in"))
      (node (ref "U1") (pin "J10") (pinfunction "NVCC_DRAM_3_J10") (pintype "power_in"))
      (node (ref "U1") (pin "J8") (pinfunction "NVCC_DRAM_4_J8") (pintype "power_in"))
      (node (ref "U1") (pin "L8") (pinfunction "NVCC_DRAM_5_L8") (pintype "power_in"))
      (node (ref "U1") (pin "N8") (pinfunction "NVCC_DRAM_6_N8") (pintype "power_in"))
      (node (ref "U1") (pin "R8") (pinfunction "NVCC_DRAM_7_R8") (pintype "power_in"))
      (node (ref "U1") (pin "U8") (pinfunction "NVCC_DRAM_8_U8") (pintype "power_in"))
      (node (ref "U1") (pin "W8") (pinfunction "NVCC_DRAM_9_W8") (pintype "power_in"))
    )
    (net (code "4") (name "NVCC_SD2") (class "Default")
      (node (ref "C15") (pin "2") (pinfunction "2_2") (pintype "passive"))
      (node (ref "U1") (pin "W24") (pinfunction "NVCC_SD2_W24") (pintype "power_in"))
    )
    (net (code "5") (name "NVCC_SNVS_1V8") (class "Default")
      (node (ref "C5") (pin "2") (pinfunction "2_2") (pintype "passive"))
      (node (ref "U1") (pin "R24") (pinfunction "NVCC_SNVS_1P8_R24") (pintype "power_in"))
    )
    (net (code "6") (name "VDDA_1V8") (class "Default")
      (node (ref "C30") (pin "2") (pinfunction "2_2") (pintype "passive"))
      (node (ref "C31") (pin "2") (pinfunction "2_2") (pintype "passive"))
      (node (ref "C32") (pin "2") (pinfunction "2_2") (pintype "passive"))
      (node (ref "C33") (pin "2") (pinfunction "2_2") (pintype "passive"))
      (node (ref "C34") (pin "2") (pinfunction "2_2") (pintype "passive"))
      (node (ref "C39") (pin "2") (pinfunction "2_2") (pintype "passive"))
      (node (ref "C40") (pin "2") (pinfunction "2_2") (pintype "passive"))
      (node (ref "C41") (pin "2") (pinfunction "2_2") (pintype "passive"))
      (node (ref "C42") (pin "2") (pinfunction "2_2") (pintype "passive"))
      (node (ref "C7") (pin "2") (pinfunction "2_2") (pintype "passive"))
      (node (ref "U1") (pin "AA20") (pinfunction "VDD_EARC_1P8_AA20") (pintype "power_in"))
      (node (ref "U1") (pin "AA22") (pinfunction "VDD_HDMI_1P8_AA22") (pintype "power_in"))
      (node (ref "U1") (pin "J19") (pinfunction "VDD_USB_1P8_J19") (pintype "passive"))
      (node (ref "U1") (pin "J20") (pinfunction "VDD_ANA0_1P8_J20") (pintype "power_in"))
      (node (ref "U1") (pin "J22") (pinfunction "VDD_LVDS_1P8_J22") (pintype "power_in"))
      (node (ref "U1") (pin "K19") (pinfunction "VDD_PCI_1P8_K19") (pintype "power_in"))
      (node (ref "U1") (pin "K20") (pinfunction "VDD_MIPI_1P8_K20") (pintype "power_in"))
      (node (ref "U1") (pin "L22") (pinfunction "VDD_24M_XTAL_1P8_L22") (pintype "power_in"))
      (node (ref "U1") (pin "N22") (pinfunction "VDD_ANA1_1P8_N22") (pintype "power_in"))
      (node (ref "U1") (pin "R6") (pinfunction "VDD_DRAM_PLL_1P8_R6") (pintype "power_in"))
      (node (ref "U1") (pin "W18") (pinfunction "VDD_SAI_PLL_1P8_W18") (pintype "power_in"))
      (node (ref "U1") (pin "W19") (pinfunction "VDD_AVPLL_1P8_W19") (pintype "power_in"))
      (node (ref "U1") (pin "Y19") (pinfunction "VDD_ARM_PLL_1P8_Y19") (pintype "power_in"))
      (node (ref "U1") (pin "Y20") (pinfunction "VDD_ANA2_1P8_Y20") (pintype "power_in"))
    )
    (net (code "7") (name "VDD_1V8") (class "Default")
      (node (ref "C132") (pin "2") (pinfunction "2_2") (pintype "passive"))
      (node (ref "C133") (pin "2") (pinfunction "2_2") (pintype "passive"))
      (node (ref "C134") (pin "2") (pinfunction "2_2") (pintype "passive"))
      (node (ref "C135") (pin "2") (pinfunction "2_2") (pintype "passive"))
      (node (ref "C136") (pin "2") (pinfunction "2_2") (pintype "passive"))
      (node (ref "C137") (pin "2") (pinfunction "2_2") (pintype "passive"))
      (node (ref "C21") (pin "2") (pinfunction "2_2") (pintype "passive"))
      (node (ref "U1") (pin "AA16") (pinfunction "PVCC2_1P8_AA16") (pintype "power_in"))
      (node (ref "U1") (pin "AA19") (pinfunction "PVCC1_1P8_AA19") (pintype "power_in"))
      (node (ref "U1") (pin "AA24") (pinfunction "NVCC_ENET_AA24") (pintype "power_in"))
      (node (ref "U1") (pin "J16") (pinfunction "PVCC0_1P8_J16") (pintype "power_in"))
      (node (ref "U1") (pin "R22") (pinfunction "NVCC_CLK_R22") (pintype "power_in"))
      (node (ref "U1") (pin "U22") (pinfunction "NVCC_NAND_U22") (pintype "power_in"))
      (node (ref "U1") (pin "U24") (pinfunction "NVCC_SD1_U24") (pintype "power_in"))
    )
    (net (code "8") (name "VDD_3V3") (class "Default")
      (node (ref "C138") (pin "2") (pinfunction "2_2") (pintype "passive"))
      (node (ref "C139") (pin "2") (pinfunction "2_2") (pintype "passive"))
      (node (ref "C140") (pin "2") (pinfunction "2_2") (pintype "passive"))
      (node (ref "C141") (pin "2") (pinfunction "2_2") (pintype "passive"))
      (node (ref "C142") (pin "2") (pinfunction "2_2") (pintype "passive"))
      (node (ref "C8") (pin "2") (pinfunction "2_2") (pintype "passive"))
      (node (ref "C9") (pin "2") (pinfunction "2_2") (pintype "passive"))
      (node (ref "U1") (pin "AA11") (pinfunction "NVCC_SAI2_SAI3_SPDIF_AA11") (pintype "power_in"))
      (node (ref "U1") (pin "AA14") (pinfunction "NVCC_ECSPI_HDMI_AA14") (pintype "power_in"))
      (node (ref "U1") (pin "J11") (pinfunction "NVCC_GPIO_J11") (pintype "power_in"))
      (node (ref "U1") (pin "J14") (pinfunction "VDD_USB_3P3_J14") (pintype "passive"))
      (node (ref "U1") (pin "K11") (pinfunction "NVCC_JTAG_K11") (pintype "power_in"))
      (node (ref "U1") (pin "Y10") (pinfunction "NVCC_I2C_UART_Y10") (pintype "power_in"))
      (node (ref "U1") (pin "Y11") (pinfunction "NVCC_SAI1_SAI5_Y11") (pintype "power_in"))
    )
    (net (code "9") (name "VDD_ARM") (class "Default")
      (node (ref "C10") (pin "2") (pinfunction "2_2") (pintype "passive"))
      (node (ref "C11") (pin "2") (pinfunction "2_2") (pintype "passive"))
      (node (ref "C12") (pin "2") (pinfunction "2_2") (pintype "passive"))
      (node (ref "C13") (pin "2") (pinfunction "2_2") (pintype "passive"))
      (node (ref "C14") (pin "2") (pinfunction "2_2") (pintype "passive"))
      (node (ref "C16") (pin "2") (pinfunction "2_2") (pintype "passive"))
      (node (ref "C17") (pin "2") (pinfunction "2_2") (pintype "passive"))
      (node (ref "C18") (pin "2") (pinfunction "2_2") (pintype "passive"))
      (node (ref "C19") (pin "2") (pinfunction "2_2") (pintype "passive"))
      (node (ref "C20") (pin "2") (pinfunction "2_2") (pintype "passive"))
      (node (ref "U1") (pin "T14") (pinfunction "VDD_ARM_1_T14") (pintype "power_in"))
      (node (ref "U1") (pin "T16") (pinfunction "VDD_ARM_2_T16") (pintype "power_in"))
      (node (ref "U1") (pin "U12") (pinfunction "VDD_ARM_3_U12") (pintype "power_in"))
      (node (ref "U1") (pin "U13") (pinfunction "VDD_ARM_4_U13") (pintype "power_in"))
      (node (ref "U1") (pin "U14") (pinfunction "VDD_ARM_5_U14") (pintype "power_in"))
      (node (ref "U1") (pin "U15") (pinfunction "VDD_ARM_6_U15") (pintype "power_in"))
      (node (ref "U1") (pin "U16") (pinfunction "VDD_ARM_7_U16") (pintype "power_in"))
      (node (ref "U1") (pin "U17") (pinfunction "VDD_ARM_8_U17") (pintype "power_in"))
      (node (ref "U1") (pin "V14") (pinfunction "VDD_ARM_9_V14") (pintype "power_in"))
      (node (ref "U1") (pin "V16") (pinfunction "VDD_ARM_10_V16") (pintype "power_in"))
      (node (ref "U1") (pin "W12") (pinfunction "VDD_ARM_11_W12") (pintype "power_in"))
      (node (ref "U1") (pin "W13") (pinfunction "VDD_ARM_12_W13") (pintype "power_in"))
      (node (ref "U1") (pin "W17") (pinfunction "VDD_ARM_13_W17") (pintype "power_in"))
      (node (ref "U1") (pin "Y14") (pinfunction "VDD_ARM_14_Y14") (pintype "power_in"))
      (node (ref "U1") (pin "Y15") (pinfunction "VDD_ARM_15_Y15") (pintype "power_in"))
      (node (ref "U1") (pin "Y16") (pinfunction "VDD_ARM_16_Y16") (pintype "power_in"))
    )
    (net (code "10") (name "VDD_SNVS_0V8") (class "Default")
      (node (ref "C6") (pin "2") (pinfunction "2_2") (pintype "passive"))
      (node (ref "U1") (pin "N26") (pinfunction "VDD_SNVS_0P8_CAP_N26") (pintype "power_in"))
    )
    (net (code "11") (name "VDD_SOC") (class "Default")
      (node (ref "C22") (pin "2") (pinfunction "2_2") (pintype "passive"))
      (node (ref "C23") (pin "2") (pinfunction "2_2") (pintype "passive"))
      (node (ref "C24") (pin "2") (pinfunction "2_2") (pintype "passive"))
      (node (ref "C25") (pin "2") (pinfunction "2_2") (pintype "passive"))
      (node (ref "C26") (pin "2") (pinfunction "2_2") (pintype "passive"))
      (node (ref "C27") (pin "2") (pinfunction "2_2") (pintype "passive"))
      (node (ref "C28") (pin "2") (pinfunction "2_2") (pintype "passive"))
      (node (ref "C29") (pin "2") (pinfunction "2_2") (pintype "passive"))
      (node (ref "C35") (pin "2") (pinfunction "2_2") (pintype "passive"))
      (node (ref "C36") (pin "2") (pinfunction "2_2") (pintype "passive"))
      (node (ref "C37") (pin "2") (pinfunction "2_2") (pintype "passive"))
      (node (ref "C38") (pin "2") (pinfunction "2_2") (pintype "passive"))
      (node (ref "C43") (pin "2") (pinfunction "2_2") (pintype "passive"))
      (node (ref "C44") (pin "2") (pinfunction "2_2") (pintype "passive"))
      (node (ref "C45") (pin "2") (pinfunction "2_2") (pintype "passive"))
      (node (ref "C46") (pin "2") (pinfunction "2_2") (pintype "passive"))
      (node (ref "C47") (pin "2") (pinfunction "2_2") (pintype "passive"))
      (node (ref "C48") (pin "2") (pinfunction "2_2") (pintype "passive"))
      (node (ref "C49") (pin "2") (pinfunction "2_2") (pintype "passive"))
      (node (ref "C50") (pin "2") (pinfunction "2_2") (pintype "passive"))
      (node (ref "U1") (pin "K10") (pinfunction "VDD_SOC_1_K10") (pintype "power_in"))
      (node (ref "U1") (pin "K14") (pinfunction "VDD_USB_0P8_K14") (pintype "passive"))
      (node (ref "U1") (pin "K15") (pinfunction "VDD_PCI_0P8_K15") (pintype "power_in"))
      (node (ref "U1") (pin "K16") (pinfunction "VDD_MIPI_0P8_K16") (pintype "power_in"))
      (node (ref "U1") (pin "L10") (pinfunction "VDD_SOC_2_L10") (pintype "power_in"))
      (node (ref "U1") (pin "L11") (pinfunction "VDD_SOC_3_L11") (pintype "power_in"))
      (node (ref "U1") (pin "L12") (pinfunction "VDD_SOC_4_L12") (pintype "power_in"))
      (node (ref "U1") (pin "L13") (pinfunction "VDD_SOC_5_L13") (pintype "power_in"))
      (node (ref "U1") (pin "L17") (pinfunction "VDD_SOC_6_L17") (pintype "power_in"))
      (node (ref "U1") (pin "L18") (pinfunction "VDD_SOC_7_L18") (pintype "power_in"))
      (node (ref "U1") (pin "L19") (pinfunction "VDD_SOC_8_L19") (pintype "power_in"))
      (node (ref "U1") (pin "L20") (pinfunction "VDD_SOC_9_L20") (pintype "power_in"))
      (node (ref "U1") (pin "L21") (pinfunction "VDD_SOC_10_L21") (pintype "power_in"))
      (node (ref "U1") (pin "L9") (pinfunction "VDD_SOC_11_L9") (pintype "power_in"))
      (node (ref "U1") (pin "M14") (pinfunction "VDD_SOC_12_M14") (pintype "power_in"))
      (node (ref "U1") (pin "M16") (pinfunction "VDD_SOC_13_M16") (pintype "power_in"))
      (node (ref "U1") (pin "N10") (pinfunction "VDD_SOC_14_N10") (pintype "power_in"))
      (node (ref "U1") (pin "N12") (pinfunction "VDD_SOC_15_N12") (pintype "power_in"))
      (node (ref "U1") (pin "N13") (pinfunction "VDD_SOC_16_N13") (pintype "power_in"))
      (node (ref "U1") (pin "N14") (pinfunction "VDD_SOC_34_N14") (pintype "power_in"))
      (node (ref "U1") (pin "N15") (pinfunction "VDD_SOC_33_N15") (pintype "power_in"))
      (node (ref "U1") (pin "N16") (pinfunction "VDD_SOC_32_N16") (pintype "power_in"))
      (node (ref "U1") (pin "N17") (pinfunction "VDD_SOC_31_N17") (pintype "power_in"))
      (node (ref "U1") (pin "N18") (pinfunction "VDD_SOC_30_N18") (pintype "power_in"))
      (node (ref "U1") (pin "N20") (pinfunction "VDD_SOC_29_N20") (pintype "power_in"))
      (node (ref "U1") (pin "N21") (pinfunction "VDD_SOC_35_N21") (pintype "power_in"))
      (node (ref "U1") (pin "N9") (pinfunction "VDD_SOC_28_N9") (pintype "power_in"))
      (node (ref "U1") (pin "P14") (pinfunction "VDD_SOC_27_P14") (pintype "power_in"))
      (node (ref "U1") (pin "P16") (pinfunction "VDD_SOC_26_P16") (pintype "power_in"))
      (node (ref "U1") (pin "R10") (pinfunction "VDD_SOC_25_R10") (pintype "power_in"))
      (node (ref "U1") (pin "R20") (pinfunction "VDD_SOC_24_R20") (pintype "power_in"))
      (node (ref "U1") (pin "R21") (pinfunction "VDD_ANA1_0P8_R21") (pintype "power_in"))
      (node (ref "U1") (pin "R9") (pinfunction "VDD_DRAM_PLL_0P8_R9") (pintype "power_in"))
      (node (ref "U1") (pin "U10") (pinfunction "VDD_SOC_23_U10") (pintype "power_in"))
      (node (ref "U1") (pin "U20") (pinfunction "VDD_SOC_22_U20") (pintype "power_in"))
      (node (ref "U1") (pin "U21") (pinfunction "VDD_SAI_PLL_0P8_U21") (pintype "power_in"))
      (node (ref "U1") (pin "U9") (pinfunction "VDD_SOC_20_U9") (pintype "power_in"))
      (node (ref "U1") (pin "W10") (pinfunction "VDD_SOC_19_W10") (pintype "power_in"))
      (node (ref "U1") (pin "W11") (pinfunction "VDD_SOC_18_W11") (pintype "power_in"))
      (node (ref "U1") (pin "W20") (pinfunction "VDD_SOC_21_W20") (pintype "power_in"))
      (node (ref "U1") (pin "W21") (pinfunction "VDD_ARM_PLL_0P8_W21") (pintype "power_in"))
      (node (ref "U1") (pin "W22") (pinfunction "VDD_HDMI_0P8_W22") (pintype "power_in"))
      (node (ref "U1") (pin "W9") (pinfunction "VDD_SOC_17_W9") (pintype "power_in"))
    )
  )
)
